# led_driver.net
KiCad netlist of a schematic drawn in EAGLE
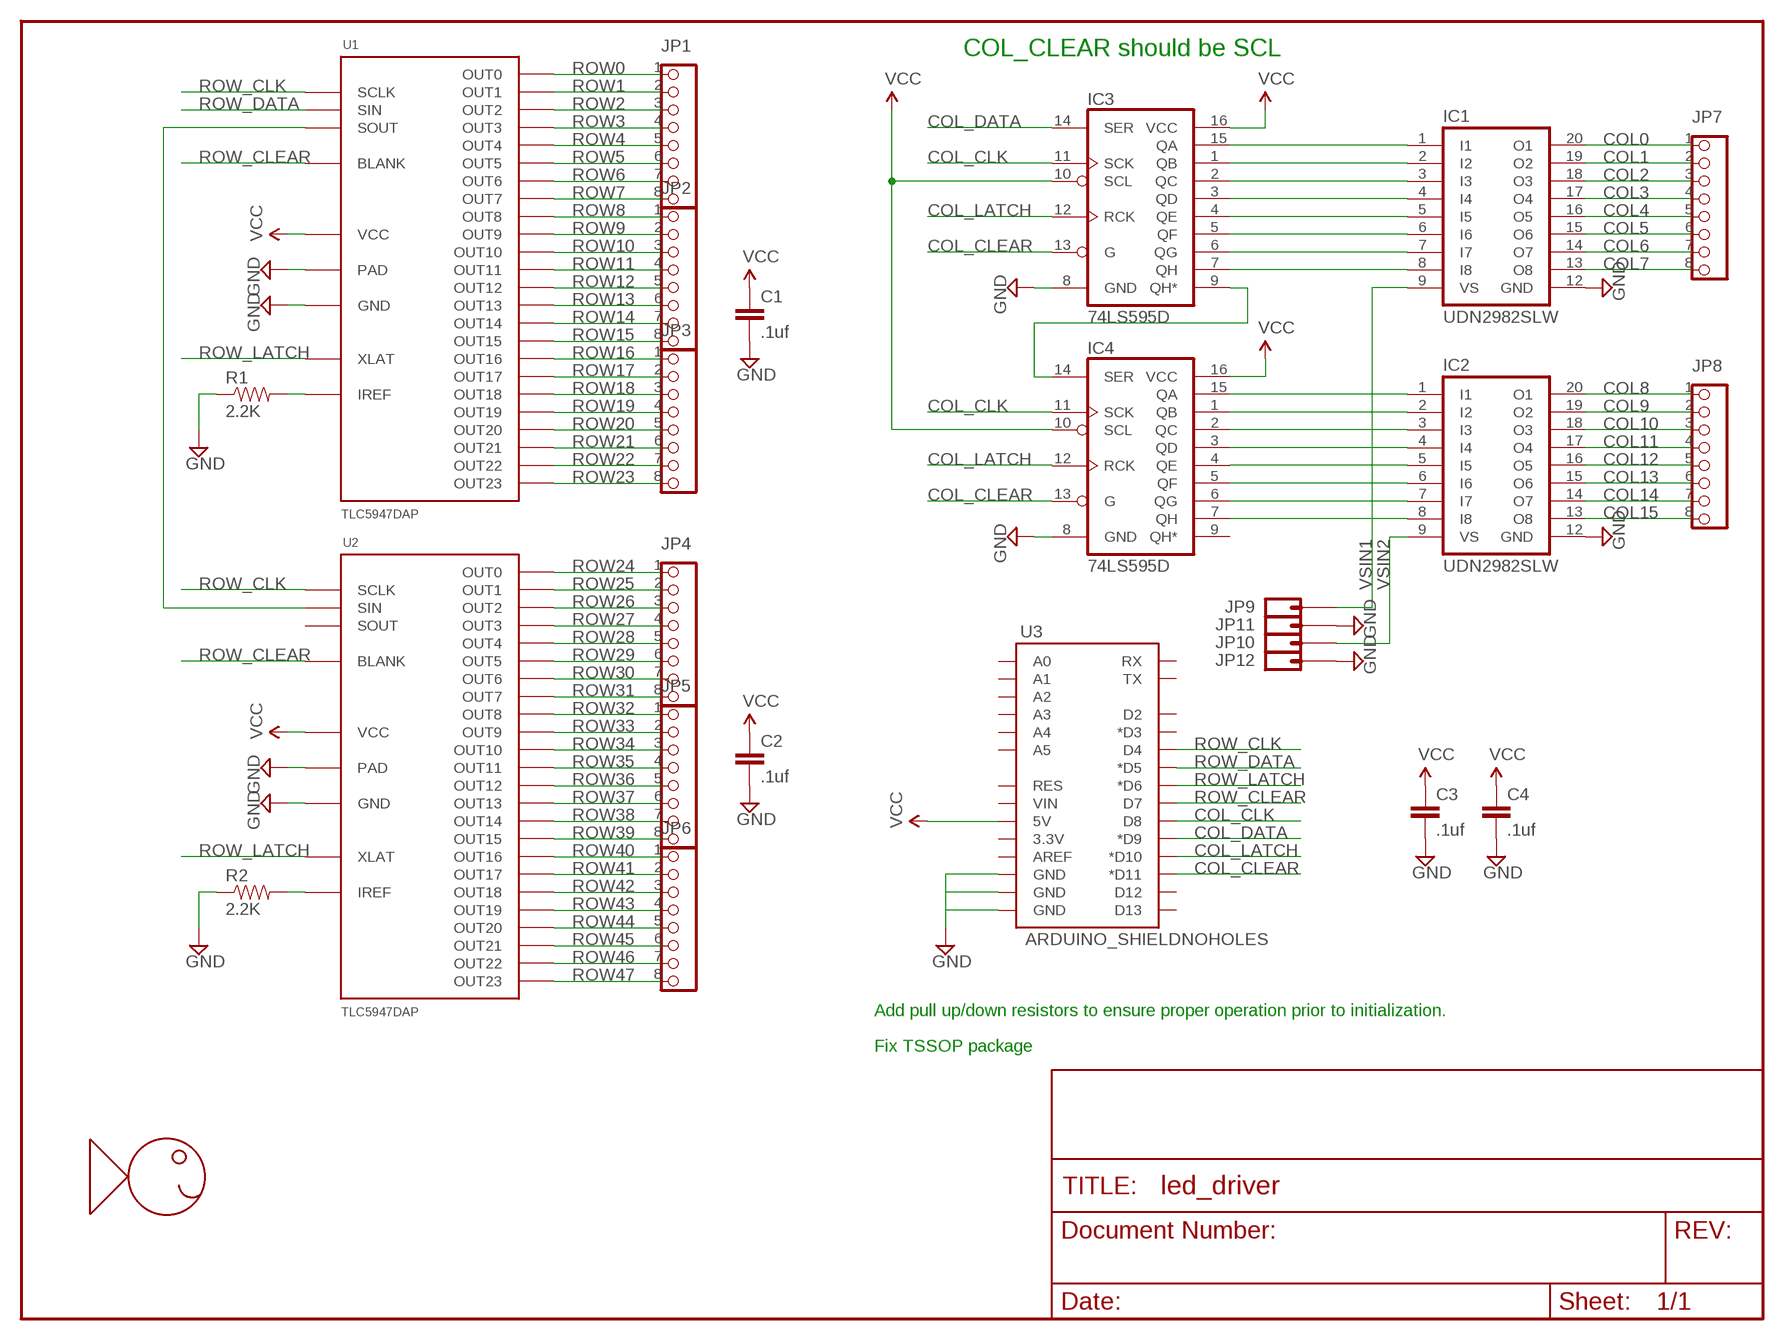
[diagram p0: schematic, sheet 1]

(export (version "E")
  (design (tool "Eeschema 10.0.6"))
  (components
    (comp (ref "C1")
      (value ".1uf")
      (footprint "eagle-import:0603-CAP")
      (libsource (lib "eagle-import") (part "CAP0603-CAP"))
    )
    (comp (ref "C2")
      (value ".1uf")
      (footprint "eagle-import:0603-CAP")
      (libsource (lib "eagle-import") (part "CAP0603-CAP"))
    )
    (comp (ref "C3")
      (value ".1uf")
      (footprint "eagle-import:0603-CAP")
      (libsource (lib "eagle-import") (part "CAP0603-CAP"))
    )
    (comp (ref "C4")
      (value ".1uf")
      (footprint "eagle-import:0603-CAP")
      (libsource (lib "eagle-import") (part "CAP0603-CAP"))
    )
    (comp (ref "IC1")
      (value "UDN2982SLW")
      (footprint "eagle-import:SO20W")
      (libsource (lib "eagle-import") (part "UDN298SLW2"))
    )
    (comp (ref "IC2")
      (value "UDN2982SLW")
      (footprint "eagle-import:SO20W")
      (libsource (lib "eagle-import") (part "UDN298SLW2"))
    )
    (comp (ref "IC3")
      (value "74LS595D")
      (footprint "eagle-import:SO16")
      (libsource (lib "eagle-import") (part "74595DLS"))
    )
    (comp (ref "IC4")
      (value "74LS595D")
      (footprint "eagle-import:SO16")
      (libsource (lib "eagle-import") (part "74595DLS"))
    )
    (comp (ref "JP1")
      (value "PINHD-1X8")
      (footprint "eagle-import:1X08")
      (libsource (lib "eagle-import") (part "PINHD-1X8"))
    )
    (comp (ref "JP2")
      (value "PINHD-1X8")
      (footprint "eagle-import:1X08")
      (libsource (lib "eagle-import") (part "PINHD-1X8"))
    )
    (comp (ref "JP3")
      (value "PINHD-1X8")
      (footprint "eagle-import:1X08")
      (libsource (lib "eagle-import") (part "PINHD-1X8"))
    )
    (comp (ref "JP4")
      (value "PINHD-1X8")
      (footprint "eagle-import:1X08")
      (libsource (lib "eagle-import") (part "PINHD-1X8"))
    )
    (comp (ref "JP5")
      (value "PINHD-1X8")
      (footprint "eagle-import:1X08")
      (libsource (lib "eagle-import") (part "PINHD-1X8"))
    )
    (comp (ref "JP6")
      (value "PINHD-1X8")
      (footprint "eagle-import:1X08")
      (libsource (lib "eagle-import") (part "PINHD-1X8"))
    )
    (comp (ref "JP7")
      (value "PINHD-1X8")
      (footprint "eagle-import:1X08")
      (libsource (lib "eagle-import") (part "PINHD-1X8"))
    )
    (comp (ref "JP8")
      (value "PINHD-1X8")
      (footprint "eagle-import:1X08")
      (libsource (lib "eagle-import") (part "PINHD-1X8"))
    )
    (comp (ref "JP9")
      (value "HEADER_01PTH")
      (footprint "eagle-import:1X01")
      (libsource (lib "eagle-import") (part "HEADER_01PTH"))
    )
    (comp (ref "JP10")
      (value "HEADER_01PTH")
      (footprint "eagle-import:1X01")
      (libsource (lib "eagle-import") (part "HEADER_01PTH"))
    )
    (comp (ref "JP11")
      (value "HEADER_01PTH")
      (footprint "eagle-import:1X01")
      (libsource (lib "eagle-import") (part "HEADER_01PTH"))
    )
    (comp (ref "JP12")
      (value "HEADER_01PTH")
      (footprint "eagle-import:1X01")
      (libsource (lib "eagle-import") (part "HEADER_01PTH"))
    )
    (comp (ref "R1")
      (value "2.2K")
      (footprint "eagle-import:0603-RES")
      (libsource (lib "eagle-import") (part "RESISTOR0603-RES"))
    )
    (comp (ref "R2")
      (value "2.2K")
      (footprint "eagle-import:0603-RES")
      (libsource (lib "eagle-import") (part "RESISTOR0603-RES"))
    )
    (comp (ref "U$1")
      (value "FHI_LOGO")
      (footprint "eagle-import:FHI_LOGO")
      (libsource (lib "eagle-import") (part "FHI_LOGO"))
    )
    (comp (ref "U1")
      (value "TLC5947DAP")
      (footprint "eagle-import:HTSSOP32DAP")
      (libsource (lib "eagle-import") (part "TLC5947DAP"))
    )
    (comp (ref "U2")
      (value "TLC5947DAP")
      (footprint "eagle-import:HTSSOP32DAP")
      (libsource (lib "eagle-import") (part "TLC5947DAP"))
    )
    (comp (ref "U3")
      (value "ARDUINO_SHIELDNOHOLES")
      (footprint "eagle-import:DUEMILANOVE_SHIELD_NOHOLES")
      (libsource (lib "eagle-import") (part "ARDUINO_SHIELDNOHOLES"))
    )
  )
  (nets
    (net (code "1") (name "/COL0") (class "Default")
      (node (ref "IC1") (pin "20") (pinfunction "O1_20") (pintype "open_collector"))
      (node (ref "JP7") (pin "1") (pinfunction "1_1") (pintype "passive"))
    )
    (net (code "2") (name "/COL1") (class "Default")
      (node (ref "IC1") (pin "19") (pinfunction "O2_19") (pintype "open_collector"))
      (node (ref "JP7") (pin "2") (pinfunction "2_2") (pintype "passive"))
    )
    (net (code "3") (name "/COL2") (class "Default")
      (node (ref "IC1") (pin "18") (pinfunction "O3_18") (pintype "open_collector"))
      (node (ref "JP7") (pin "3") (pinfunction "3_3") (pintype "passive"))
    )
    (net (code "4") (name "/COL3") (class "Default")
      (node (ref "IC1") (pin "17") (pinfunction "O4_17") (pintype "open_collector"))
      (node (ref "JP7") (pin "4") (pinfunction "4_4") (pintype "passive"))
    )
    (net (code "5") (name "/COL4") (class "Default")
      (node (ref "IC1") (pin "16") (pinfunction "O5_16") (pintype "open_collector"))
      (node (ref "JP7") (pin "5") (pinfunction "5_5") (pintype "passive"))
    )
    (net (code "6") (name "/COL5") (class "Default")
      (node (ref "IC1") (pin "15") (pinfunction "O6_15") (pintype "open_collector"))
      (node (ref "JP7") (pin "6") (pinfunction "6_6") (pintype "passive"))
    )
    (net (code "7") (name "/COL6") (class "Default")
      (node (ref "IC1") (pin "14") (pinfunction "O7_14") (pintype "open_collector"))
      (node (ref "JP7") (pin "7") (pinfunction "7_7") (pintype "passive"))
    )
    (net (code "8") (name "/COL7") (class "Default")
      (node (ref "IC1") (pin "13") (pinfunction "O8_13") (pintype "open_collector"))
      (node (ref "JP7") (pin "8") (pinfunction "8_8") (pintype "passive"))
    )
    (net (code "9") (name "/COL8") (class "Default")
      (node (ref "IC2") (pin "20") (pinfunction "O1_20") (pintype "open_collector"))
      (node (ref "JP8") (pin "1") (pinfunction "1_1") (pintype "passive"))
    )
    (net (code "10") (name "/COL9") (class "Default")
      (node (ref "IC2") (pin "19") (pinfunction "O2_19") (pintype "open_collector"))
      (node (ref "JP8") (pin "2") (pinfunction "2_2") (pintype "passive"))
    )
    (net (code "11") (name "/COL10") (class "Default")
      (node (ref "IC2") (pin "18") (pinfunction "O3_18") (pintype "open_collector"))
      (node (ref "JP8") (pin "3") (pinfunction "3_3") (pintype "passive"))
    )
    (net (code "12") (name "/COL11") (class "Default")
      (node (ref "IC2") (pin "17") (pinfunction "O4_17") (pintype "open_collector"))
      (node (ref "JP8") (pin "4") (pinfunction "4_4") (pintype "passive"))
    )
    (net (code "13") (name "/COL12") (class "Default")
      (node (ref "IC2") (pin "16") (pinfunction "O5_16") (pintype "open_collector"))
      (node (ref "JP8") (pin "5") (pinfunction "5_5") (pintype "passive"))
    )
    (net (code "14") (name "/COL13") (class "Default")
      (node (ref "IC2") (pin "15") (pinfunction "O6_15") (pintype "open_collector"))
      (node (ref "JP8") (pin "6") (pinfunction "6_6") (pintype "passive"))
    )
    (net (code "15") (name "/COL14") (class "Default")
      (node (ref "IC2") (pin "14") (pinfunction "O7_14") (pintype "open_collector"))
      (node (ref "JP8") (pin "7") (pinfunction "7_7") (pintype "passive"))
    )
    (net (code "16") (name "/COL15") (class "Default")
      (node (ref "IC2") (pin "13") (pinfunction "O8_13") (pintype "open_collector"))
      (node (ref "JP8") (pin "8") (pinfunction "8_8") (pintype "passive"))
    )
    (net (code "17") (name "/COL_CLEAR") (class "Default")
      (node (ref "IC3") (pin "13") (pinfunction "G_13") (pintype "input"))
      (node (ref "IC4") (pin "13") (pinfunction "G_13") (pintype "input"))
      (node (ref "U3") (pin "D11") (pinfunction "*D11_D11") (pintype "bidirectional"))
    )
    (net (code "18") (name "/COL_CLK") (class "Default")
      (node (ref "IC3") (pin "11") (pinfunction "SCK_11") (pintype "input"))
      (node (ref "IC4") (pin "11") (pinfunction "SCK_11") (pintype "input"))
      (node (ref "U3") (pin "D8") (pinfunction "D8_D8") (pintype "bidirectional"))
    )
    (net (code "19") (name "/COL_DATA") (class "Default")
      (node (ref "IC3") (pin "14") (pinfunction "SER_14") (pintype "input"))
      (node (ref "U3") (pin "D9") (pinfunction "*D9_D9") (pintype "bidirectional"))
    )
    (net (code "20") (name "/COL_LATCH") (class "Default")
      (node (ref "IC3") (pin "12") (pinfunction "RCK_12") (pintype "input"))
      (node (ref "IC4") (pin "12") (pinfunction "RCK_12") (pintype "input"))
      (node (ref "U3") (pin "D10") (pinfunction "*D10_D10") (pintype "bidirectional"))
    )
    (net (code "21") (name "/ROW0") (class "Default")
      (node (ref "JP1") (pin "1") (pinfunction "1_1") (pintype "passive"))
      (node (ref "U1") (pin "5") (pinfunction "OUT0_5") (pintype "bidirectional"))
    )
    (net (code "22") (name "/ROW1") (class "Default")
      (node (ref "JP1") (pin "2") (pinfunction "2_2") (pintype "passive"))
      (node (ref "U1") (pin "6") (pinfunction "OUT1_6") (pintype "bidirectional"))
    )
    (net (code "23") (name "/ROW2") (class "Default")
      (node (ref "JP1") (pin "3") (pinfunction "3_3") (pintype "passive"))
      (node (ref "U1") (pin "7") (pinfunction "OUT2_7") (pintype "bidirectional"))
    )
    (net (code "24") (name "/ROW3") (class "Default")
      (node (ref "JP1") (pin "4") (pinfunction "4_4") (pintype "passive"))
      (node (ref "U1") (pin "8") (pinfunction "OUT3_8") (pintype "bidirectional"))
    )
    (net (code "25") (name "/ROW4") (class "Default")
      (node (ref "JP1") (pin "5") (pinfunction "5_5") (pintype "passive"))
      (node (ref "U1") (pin "9") (pinfunction "OUT4_9") (pintype "bidirectional"))
    )
    (net (code "26") (name "/ROW5") (class "Default")
      (node (ref "JP1") (pin "6") (pinfunction "6_6") (pintype "passive"))
      (node (ref "U1") (pin "10") (pinfunction "OUT5_10") (pintype "bidirectional"))
    )
    (net (code "27") (name "/ROW6") (class "Default")
      (node (ref "JP1") (pin "7") (pinfunction "7_7") (pintype "passive"))
      (node (ref "U1") (pin "11") (pinfunction "OUT6_11") (pintype "bidirectional"))
    )
    (net (code "28") (name "/ROW7") (class "Default")
      (node (ref "JP1") (pin "8") (pinfunction "8_8") (pintype "passive"))
      (node (ref "U1") (pin "12") (pinfunction "OUT7_12") (pintype "bidirectional"))
    )
    (net (code "29") (name "/ROW8") (class "Default")
      (node (ref "JP2") (pin "1") (pinfunction "1_1") (pintype "passive"))
      (node (ref "U1") (pin "13") (pinfunction "OUT8_13") (pintype "bidirectional"))
    )
    (net (code "30") (name "/ROW9") (class "Default")
      (node (ref "JP2") (pin "2") (pinfunction "2_2") (pintype "passive"))
      (node (ref "U1") (pin "14") (pinfunction "OUT9_14") (pintype "bidirectional"))
    )
    (net (code "31") (name "/ROW10") (class "Default")
      (node (ref "JP2") (pin "3") (pinfunction "3_3") (pintype "passive"))
      (node (ref "U1") (pin "15") (pinfunction "OUT10_15") (pintype "bidirectional"))
    )
    (net (code "32") (name "/ROW11") (class "Default")
      (node (ref "JP2") (pin "4") (pinfunction "4_4") (pintype "passive"))
      (node (ref "U1") (pin "16") (pinfunction "OUT11_16") (pintype "bidirectional"))
    )
    (net (code "33") (name "/ROW12") (class "Default")
      (node (ref "JP2") (pin "5") (pinfunction "5_5") (pintype "passive"))
      (node (ref "U1") (pin "17") (pinfunction "OUT12_17") (pintype "bidirectional"))
    )
    (net (code "34") (name "/ROW13") (class "Default")
      (node (ref "JP2") (pin "6") (pinfunction "6_6") (pintype "passive"))
      (node (ref "U1") (pin "18") (pinfunction "OUT13_18") (pintype "bidirectional"))
    )
    (net (code "35") (name "/ROW14") (class "Default")
      (node (ref "JP2") (pin "7") (pinfunction "7_7") (pintype "passive"))
      (node (ref "U1") (pin "19") (pinfunction "OUT14_19") (pintype "bidirectional"))
    )
    (net (code "36") (name "/ROW15") (class "Default")
      (node (ref "JP2") (pin "8") (pinfunction "8_8") (pintype "passive"))
      (node (ref "U1") (pin "20") (pinfunction "OUT15_20") (pintype "bidirectional"))
    )
    (net (code "37") (name "/ROW16") (class "Default")
      (node (ref "JP3") (pin "1") (pinfunction "1_1") (pintype "passive"))
      (node (ref "U1") (pin "21") (pinfunction "OUT16_21") (pintype "bidirectional"))
    )
    (net (code "38") (name "/ROW17") (class "Default")
      (node (ref "JP3") (pin "2") (pinfunction "2_2") (pintype "passive"))
      (node (ref "U1") (pin "22") (pinfunction "OUT17_22") (pintype "bidirectional"))
    )
    (net (code "39") (name "/ROW18") (class "Default")
      (node (ref "JP3") (pin "3") (pinfunction "3_3") (pintype "passive"))
      (node (ref "U1") (pin "23") (pinfunction "OUT18_23") (pintype "bidirectional"))
    )
    (net (code "40") (name "/ROW19") (class "Default")
      (node (ref "JP3") (pin "4") (pinfunction "4_4") (pintype "passive"))
      (node (ref "U1") (pin "24") (pinfunction "OUT19_24") (pintype "bidirectional"))
    )
    (net (code "41") (name "/ROW20") (class "Default")
      (node (ref "JP3") (pin "5") (pinfunction "5_5") (pintype "passive"))
      (node (ref "U1") (pin "25") (pinfunction "OUT20_25") (pintype "bidirectional"))
    )
    (net (code "42") (name "/ROW21") (class "Default")
      (node (ref "JP3") (pin "6") (pinfunction "6_6") (pintype "passive"))
      (node (ref "U1") (pin "26") (pinfunction "OUT21_26") (pintype "bidirectional"))
    )
    (net (code "43") (name "/ROW22") (class "Default")
      (node (ref "JP3") (pin "7") (pinfunction "7_7") (pintype "passive"))
      (node (ref "U1") (pin "27") (pinfunction "OUT22_27") (pintype "bidirectional"))
    )
    (net (code "44") (name "/ROW23") (class "Default")
      (node (ref "JP3") (pin "8") (pinfunction "8_8") (pintype "passive"))
      (node (ref "U1") (pin "28") (pinfunction "OUT23_28") (pintype "bidirectional"))
    )
    (net (code "45") (name "/ROW24") (class "Default")
      (node (ref "JP4") (pin "1") (pinfunction "1_1") (pintype "passive"))
      (node (ref "U2") (pin "5") (pinfunction "OUT0_5") (pintype "bidirectional"))
    )
    (net (code "46") (name "/ROW25") (class "Default")
      (node (ref "JP4") (pin "2") (pinfunction "2_2") (pintype "passive"))
      (node (ref "U2") (pin "6") (pinfunction "OUT1_6") (pintype "bidirectional"))
    )
    (net (code "47") (name "/ROW26") (class "Default")
      (node (ref "JP4") (pin "3") (pinfunction "3_3") (pintype "passive"))
      (node (ref "U2") (pin "7") (pinfunction "OUT2_7") (pintype "bidirectional"))
    )
    (net (code "48") (name "/ROW27") (class "Default")
      (node (ref "JP4") (pin "4") (pinfunction "4_4") (pintype "passive"))
      (node (ref "U2") (pin "8") (pinfunction "OUT3_8") (pintype "bidirectional"))
    )
    (net (code "49") (name "/ROW28") (class "Default")
      (node (ref "JP4") (pin "5") (pinfunction "5_5") (pintype "passive"))
      (node (ref "U2") (pin "9") (pinfunction "OUT4_9") (pintype "bidirectional"))
    )
    (net (code "50") (name "/ROW29") (class "Default")
      (node (ref "JP4") (pin "6") (pinfunction "6_6") (pintype "passive"))
      (node (ref "U2") (pin "10") (pinfunction "OUT5_10") (pintype "bidirectional"))
    )
    (net (code "51") (name "/ROW30") (class "Default")
      (node (ref "JP4") (pin "7") (pinfunction "7_7") (pintype "passive"))
      (node (ref "U2") (pin "11") (pinfunction "OUT6_11") (pintype "bidirectional"))
    )
    (net (code "52") (name "/ROW31") (class "Default")
      (node (ref "JP4") (pin "8") (pinfunction "8_8") (pintype "passive"))
      (node (ref "U2") (pin "12") (pinfunction "OUT7_12") (pintype "bidirectional"))
    )
    (net (code "53") (name "/ROW32") (class "Default")
      (node (ref "JP5") (pin "1") (pinfunction "1_1") (pintype "passive"))
      (node (ref "U2") (pin "13") (pinfunction "OUT8_13") (pintype "bidirectional"))
    )
    (net (code "54") (name "/ROW33") (class "Default")
      (node (ref "JP5") (pin "2") (pinfunction "2_2") (pintype "passive"))
      (node (ref "U2") (pin "14") (pinfunction "OUT9_14") (pintype "bidirectional"))
    )
    (net (code "55") (name "/ROW34") (class "Default")
      (node (ref "JP5") (pin "3") (pinfunction "3_3") (pintype "passive"))
      (node (ref "U2") (pin "15") (pinfunction "OUT10_15") (pintype "bidirectional"))
    )
    (net (code "56") (name "/ROW35") (class "Default")
      (node (ref "JP5") (pin "4") (pinfunction "4_4") (pintype "passive"))
      (node (ref "U2") (pin "16") (pinfunction "OUT11_16") (pintype "bidirectional"))
    )
    (net (code "57") (name "/ROW36") (class "Default")
      (node (ref "JP5") (pin "5") (pinfunction "5_5") (pintype "passive"))
      (node (ref "U2") (pin "17") (pinfunction "OUT12_17") (pintype "bidirectional"))
    )
    (net (code "58") (name "/ROW37") (class "Default")
      (node (ref "JP5") (pin "6") (pinfunction "6_6") (pintype "passive"))
      (node (ref "U2") (pin "18") (pinfunction "OUT13_18") (pintype "bidirectional"))
    )
    (net (code "59") (name "/ROW38") (class "Default")
      (node (ref "JP5") (pin "7") (pinfunction "7_7") (pintype "passive"))
      (node (ref "U2") (pin "19") (pinfunction "OUT14_19") (pintype "bidirectional"))
    )
    (net (code "60") (name "/ROW39") (class "Default")
      (node (ref "JP5") (pin "8") (pinfunction "8_8") (pintype "passive"))
      (node (ref "U2") (pin "20") (pinfunction "OUT15_20") (pintype "bidirectional"))
    )
    (net (code "61") (name "/ROW40") (class "Default")
      (node (ref "JP6") (pin "1") (pinfunction "1_1") (pintype "passive"))
      (node (ref "U2") (pin "21") (pinfunction "OUT16_21") (pintype "bidirectional"))
    )
    (net (code "62") (name "/ROW41") (class "Default")
      (node (ref "JP6") (pin "2") (pinfunction "2_2") (pintype "passive"))
      (node (ref "U2") (pin "22") (pinfunction "OUT17_22") (pintype "bidirectional"))
    )
    (net (code "63") (name "/ROW42") (class "Default")
      (node (ref "JP6") (pin "3") (pinfunction "3_3") (pintype "passive"))
      (node (ref "U2") (pin "23") (pinfunction "OUT18_23") (pintype "bidirectional"))
    )
    (net (code "64") (name "/ROW43") (class "Default")
      (node (ref "JP6") (pin "4") (pinfunction "4_4") (pintype "passive"))
      (node (ref "U2") (pin "24") (pinfunction "OUT19_24") (pintype "bidirectional"))
    )
    (net (code "65") (name "/ROW44") (class "Default")
      (node (ref "JP6") (pin "5") (pinfunction "5_5") (pintype "passive"))
      (node (ref "U2") (pin "25") (pinfunction "OUT20_25") (pintype "bidirectional"))
    )
    (net (code "66") (name "/ROW45") (class "Default")
      (node (ref "JP6") (pin "6") (pinfunction "6_6") (pintype "passive"))
      (node (ref "U2") (pin "26") (pinfunction "OUT21_26") (pintype "bidirectional"))
    )
    (net (code "67") (name "/ROW46") (class "Default")
      (node (ref "JP6") (pin "7") (pinfunction "7_7") (pintype "passive"))
      (node (ref "U2") (pin "27") (pinfunction "OUT22_27") (pintype "bidirectional"))
    )
    (net (code "68") (name "/ROW47") (class "Default")
      (node (ref "JP6") (pin "8") (pinfunction "8_8") (pintype "passive"))
      (node (ref "U2") (pin "28") (pinfunction "OUT23_28") (pintype "bidirectional"))
    )
    (net (code "69") (name "/ROW_CLEAR") (class "Default")
      (node (ref "U1") (pin "2") (pinfunction "BLANK_2") (pintype "bidirectional"))
      (node (ref "U2") (pin "2") (pinfunction "BLANK_2") (pintype "bidirectional"))
      (node (ref "U3") (pin "D7") (pinfunction "D7_D7") (pintype "bidirectional"))
    )
    (net (code "70") (name "/ROW_CLK") (class "Default")
      (node (ref "U1") (pin "3") (pinfunction "SCLK_3") (pintype "bidirectional"))
      (node (ref "U2") (pin "3") (pinfunction "SCLK_3") (pintype "bidirectional"))
      (node (ref "U3") (pin "D4") (pinfunction "D4_D4") (pintype "bidirectional"))
    )
    (net (code "71") (name "/ROW_DATA") (class "Default")
      (node (ref "U1") (pin "4") (pinfunction "SIN_4") (pintype "bidirectional"))
      (node (ref "U3") (pin "D5") (pinfunction "*D5_D5") (pintype "bidirectional"))
    )
    (net (code "72") (name "/ROW_LATCH") (class "Default")
      (node (ref "U1") (pin "30") (pinfunction "XLAT_30") (pintype "bidirectional"))
      (node (ref "U2") (pin "30") (pinfunction "XLAT_30") (pintype "bidirectional"))
      (node (ref "U3") (pin "D6") (pinfunction "*D6_D6") (pintype "bidirectional"))
    )
    (net (code "73") (name "/VSIN1") (class "Default")
      (node (ref "IC1") (pin "9") (pinfunction "VS_9") (pintype "passive"))
      (node (ref "JP9") (pin "1") (pinfunction "1_1") (pintype "passive"))
    )
    (net (code "74") (name "/VSIN2") (class "Default")
      (node (ref "IC2") (pin "9") (pinfunction "VS_9") (pintype "passive"))
      (node (ref "JP10") (pin "1") (pinfunction "1_1") (pintype "passive"))
    )
    (net (code "75") (name "GND") (class "Default")
      (node (ref "C1") (pin "2") (pinfunction "2_2") (pintype "passive"))
      (node (ref "C2") (pin "2") (pinfunction "2_2") (pintype "passive"))
      (node (ref "C3") (pin "2") (pinfunction "2_2") (pintype "passive"))
      (node (ref "C4") (pin "2") (pinfunction "2_2") (pintype "passive"))
      (node (ref "IC1") (pin "12") (pinfunction "GND_12") (pintype "power_in"))
      (node (ref "IC2") (pin "12") (pinfunction "GND_12") (pintype "power_in"))
      (node (ref "IC3") (pin "8") (pinfunction "GND_8") (pintype "power_in"))
      (node (ref "IC4") (pin "8") (pinfunction "GND_8") (pintype "power_in"))
      (node (ref "JP11") (pin "1") (pinfunction "1_1") (pintype "passive"))
      (node (ref "JP12") (pin "1") (pinfunction "1_1") (pintype "passive"))
      (node (ref "R1") (pin "1") (pinfunction "1_1") (pintype "passive"))
      (node (ref "R2") (pin "1") (pinfunction "1_1") (pintype "passive"))
      (node (ref "U1") (pin "1") (pinfunction "GND_1") (pintype "bidirectional"))
      (node (ref "U1") (pin "EXP") (pinfunction "PAD_EXP") (pintype "bidirectional"))
      (node (ref "U2") (pin "1") (pinfunction "GND_1") (pintype "bidirectional"))
      (node (ref "U2") (pin "EXP") (pinfunction "PAD_EXP") (pintype "bidirectional"))
      (node (ref "U3") (pin "GND@0") (pinfunction "GND_GND@0") (pintype "bidirectional"))
      (node (ref "U3") (pin "GND@1") (pinfunction "GND_GND@1") (pintype "bidirectional"))
      (node (ref "U3") (pin "GND@2") (pinfunction "GND_GND@2") (pintype "bidirectional"))
    )
    (net (code "76") (name "Net-(IC1-I1)") (class "Default")
      (node (ref "IC1") (pin "1") (pinfunction "I1_1") (pintype "input"))
      (node (ref "IC3") (pin "15") (pinfunction "QA_15") (pintype "tri_state"))
    )
    (net (code "77") (name "Net-(IC1-I2)") (class "Default")
      (node (ref "IC1") (pin "2") (pinfunction "I2_2") (pintype "input"))
      (node (ref "IC3") (pin "1") (pinfunction "QB_1") (pintype "tri_state"))
    )
    (net (code "78") (name "Net-(IC1-I3)") (class "Default")
      (node (ref "IC1") (pin "3") (pinfunction "I3_3") (pintype "input"))
      (node (ref "IC3") (pin "2") (pinfunction "QC_2") (pintype "tri_state"))
    )
    (net (code "79") (name "Net-(IC1-I4)") (class "Default")
      (node (ref "IC1") (pin "4") (pinfunction "I4_4") (pintype "input"))
      (node (ref "IC3") (pin "3") (pinfunction "QD_3") (pintype "tri_state"))
    )
    (net (code "80") (name "Net-(IC1-I5)") (class "Default")
      (node (ref "IC1") (pin "5") (pinfunction "I5_5") (pintype "input"))
      (node (ref "IC3") (pin "4") (pinfunction "QE_4") (pintype "tri_state"))
    )
    (net (code "81") (name "Net-(IC1-I6)") (class "Default")
      (node (ref "IC1") (pin "6") (pinfunction "I6_6") (pintype "input"))
      (node (ref "IC3") (pin "5") (pinfunction "QF_5") (pintype "tri_state"))
    )
    (net (code "82") (name "Net-(IC1-I7)") (class "Default")
      (node (ref "IC1") (pin "7") (pinfunction "I7_7") (pintype "input"))
      (node (ref "IC3") (pin "6") (pinfunction "QG_6") (pintype "tri_state"))
    )
    (net (code "83") (name "Net-(IC1-I8)") (class "Default")
      (node (ref "IC1") (pin "8") (pinfunction "I8_8") (pintype "input"))
      (node (ref "IC3") (pin "7") (pinfunction "QH_7") (pintype "tri_state"))
    )
    (net (code "84") (name "Net-(IC2-I1)") (class "Default")
      (node (ref "IC2") (pin "1") (pinfunction "I1_1") (pintype "input"))
      (node (ref "IC4") (pin "15") (pinfunction "QA_15") (pintype "tri_state"))
    )
    (net (code "85") (name "Net-(IC2-I2)") (class "Default")
      (node (ref "IC2") (pin "2") (pinfunction "I2_2") (pintype "input"))
      (node (ref "IC4") (pin "1") (pinfunction "QB_1") (pintype "tri_state"))
    )
    (net (code "86") (name "Net-(IC2-I3)") (class "Default")
      (node (ref "IC2") (pin "3") (pinfunction "I3_3") (pintype "input"))
      (node (ref "IC4") (pin "2") (pinfunction "QC_2") (pintype "tri_state"))
    )
    (net (code "87") (name "Net-(IC2-I4)") (class "Default")
      (node (ref "IC2") (pin "4") (pinfunction "I4_4") (pintype "input"))
      (node (ref "IC4") (pin "3") (pinfunction "QD_3") (pintype "tri_state"))
    )
    (net (code "88") (name "Net-(IC2-I5)") (class "Default")
      (node (ref "IC2") (pin "5") (pinfunction "I5_5") (pintype "input"))
      (node (ref "IC4") (pin "4") (pinfunction "QE_4") (pintype "tri_state"))
    )
    (net (code "89") (name "Net-(IC2-I6)") (class "Default")
      (node (ref "IC2") (pin "6") (pinfunction "I6_6") (pintype "input"))
      (node (ref "IC4") (pin "5") (pinfunction "QF_5") (pintype "tri_state"))
    )
    (net (code "90") (name "Net-(IC2-I7)") (class "Default")
      (node (ref "IC2") (pin "7") (pinfunction "I7_7") (pintype "input"))
      (node (ref "IC4") (pin "6") (pinfunction "QG_6") (pintype "tri_state"))
    )
    (net (code "91") (name "Net-(IC2-I8)") (class "Default")
      (node (ref "IC2") (pin "8") (pinfunction "I8_8") (pintype "input"))
      (node (ref "IC4") (pin "7") (pinfunction "QH_7") (pintype "tri_state"))
    )
    (net (code "92") (name "Net-(IC3-QH*)") (class "Default")
      (node (ref "IC3") (pin "9") (pinfunction "QH*_9") (pintype "tri_state"))
      (node (ref "IC4") (pin "14") (pinfunction "SER_14") (pintype "input"))
    )
    (net (code "93") (name "Net-(U1-IREF)") (class "Default")
      (node (ref "R1") (pin "2") (pinfunction "2_2") (pintype "passive"))
      (node (ref "U1") (pin "31") (pinfunction "IREF_31") (pintype "bidirectional"))
    )
    (net (code "94") (name "Net-(U1-SOUT)") (class "Default")
      (node (ref "U1") (pin "29") (pinfunction "SOUT_29") (pintype "bidirectional"))
      (node (ref "U2") (pin "4") (pinfunction "SIN_4") (pintype "bidirectional"))
    )
    (net (code "95") (name "Net-(U2-IREF)") (class "Default")
      (node (ref "R2") (pin "2") (pinfunction "2_2") (pintype "passive"))
      (node (ref "U2") (pin "31") (pinfunction "IREF_31") (pintype "bidirectional"))
    )
    (net (code "96") (name "VCC") (class "Default")
      (node (ref "C1") (pin "1") (pinfunction "1_1") (pintype "passive"))
      (node (ref "C2") (pin "1") (pinfunction "1_1") (pintype "passive"))
      (node (ref "C3") (pin "1") (pinfunction "1_1") (pintype "passive"))
      (node (ref "C4") (pin "1") (pinfunction "1_1") (pintype "passive"))
      (node (ref "IC3") (pin "10") (pinfunction "SCL_10") (pintype "input"))
      (node (ref "IC3") (pin "16") (pinfunction "VCC_16") (pintype "power_in"))
      (node (ref "IC4") (pin "10") (pinfunction "SCL_10") (pintype "input"))
      (node (ref "IC4") (pin "16") (pinfunction "VCC_16") (pintype "power_in"))
      (node (ref "U1") (pin "32") (pinfunction "VCC_32") (pintype "bidirectional"))
      (node (ref "U2") (pin "32") (pinfunction "VCC_32") (pintype "bidirectional"))
      (node (ref "U3") (pin "5V") (pinfunction "5V_5V") (pintype "bidirectional"))
    )
    (net (code "97") (name "unconnected-(IC4-QH*-Pad9)") (class "Default")
      (node (ref "IC4") (pin "9") (pinfunction "QH*_9") (pintype "tri_state"))
    )
    (net (code "98") (name "unconnected-(U2-SOUT-Pad29)") (class "Default")
      (node (ref "U2") (pin "29") (pinfunction "SOUT_29") (pintype "bidirectional"))
    )
    (net (code "99") (name "unconnected-(U3-*D3-PadD3)") (class "Default")
      (node (ref "U3") (pin "D3") (pinfunction "*D3_D3") (pintype "bidirectional"))
    )
    (net (code "100") (name "unconnected-(U3-Pad3.3V)") (class "Default")
      (node (ref "U3") (pin "3.3V") (pinfunction "3.3V_3.3V") (pintype "bidirectional"))
    )
    (net (code "101") (name "unconnected-(U3-PadA0)") (class "Default")
      (node (ref "U3") (pin "A0") (pinfunction "A0_A0") (pintype "bidirectional"))
    )
    (net (code "102") (name "unconnected-(U3-PadA1)") (class "Default")
      (node (ref "U3") (pin "A1") (pinfunction "A1_A1") (pintype "bidirectional"))
    )
    (net (code "103") (name "unconnected-(U3-PadA2)") (class "Default")
      (node (ref "U3") (pin "A2") (pinfunction "A2_A2") (pintype "bidirectional"))
    )
    (net (code "104") (name "unconnected-(U3-PadA3)") (class "Default")
      (node (ref "U3") (pin "A3") (pinfunction "A3_A3") (pintype "bidirectional"))
    )
    (net (code "105") (name "unconnected-(U3-PadA4)") (class "Default")
      (node (ref "U3") (pin "A4") (pinfunction "A4_A4") (pintype "bidirectional"))
    )
    (net (code "106") (name "unconnected-(U3-PadA5)") (class "Default")
      (node (ref "U3") (pin "A5") (pinfunction "A5_A5") (pintype "bidirectional"))
    )
    (net (code "107") (name "unconnected-(U3-PadAREF)") (class "Default")
      (node (ref "U3") (pin "AREF") (pinfunction "AREF_AREF") (pintype "bidirectional"))
    )
    (net (code "108") (name "unconnected-(U3-PadD2)") (class "Default")
      (node (ref "U3") (pin "D2") (pinfunction "D2_D2") (pintype "bidirectional"))
    )
    (net (code "109") (name "unconnected-(U3-PadD12)") (class "Default")
      (node (ref "U3") (pin "D12") (pinfunction "D12_D12") (pintype "bidirectional"))
    )
    (net (code "110") (name "unconnected-(U3-PadD13)") (class "Default")
      (node (ref "U3") (pin "D13") (pinfunction "D13_D13") (pintype "bidirectional"))
    )
    (net (code "111") (name "unconnected-(U3-PadRES)") (class "Default")
      (node (ref "U3") (pin "RES") (pinfunction "RES_RES") (pintype "bidirectional"))
    )
    (net (code "112") (name "unconnected-(U3-PadRX)") (class "Default")
      (node (ref "U3") (pin "RX") (pinfunction "RX_RX") (pintype "bidirectional"))
    )
    (net (code "113") (name "unconnected-(U3-PadTX)") (class "Default")
      (node (ref "U3") (pin "TX") (pinfunction "TX_TX") (pintype "bidirectional"))
    )
    (net (code "114") (name "unconnected-(U3-PadVIN)") (class "Default")
      (node (ref "U3") (pin "VIN") (pinfunction "VIN_VIN") (pintype "bidirectional"))
    )
  )
)
